# STRWL-S02-V00-12VProtection.net
KiCad netlist of a schematic drawn in Altium Designer
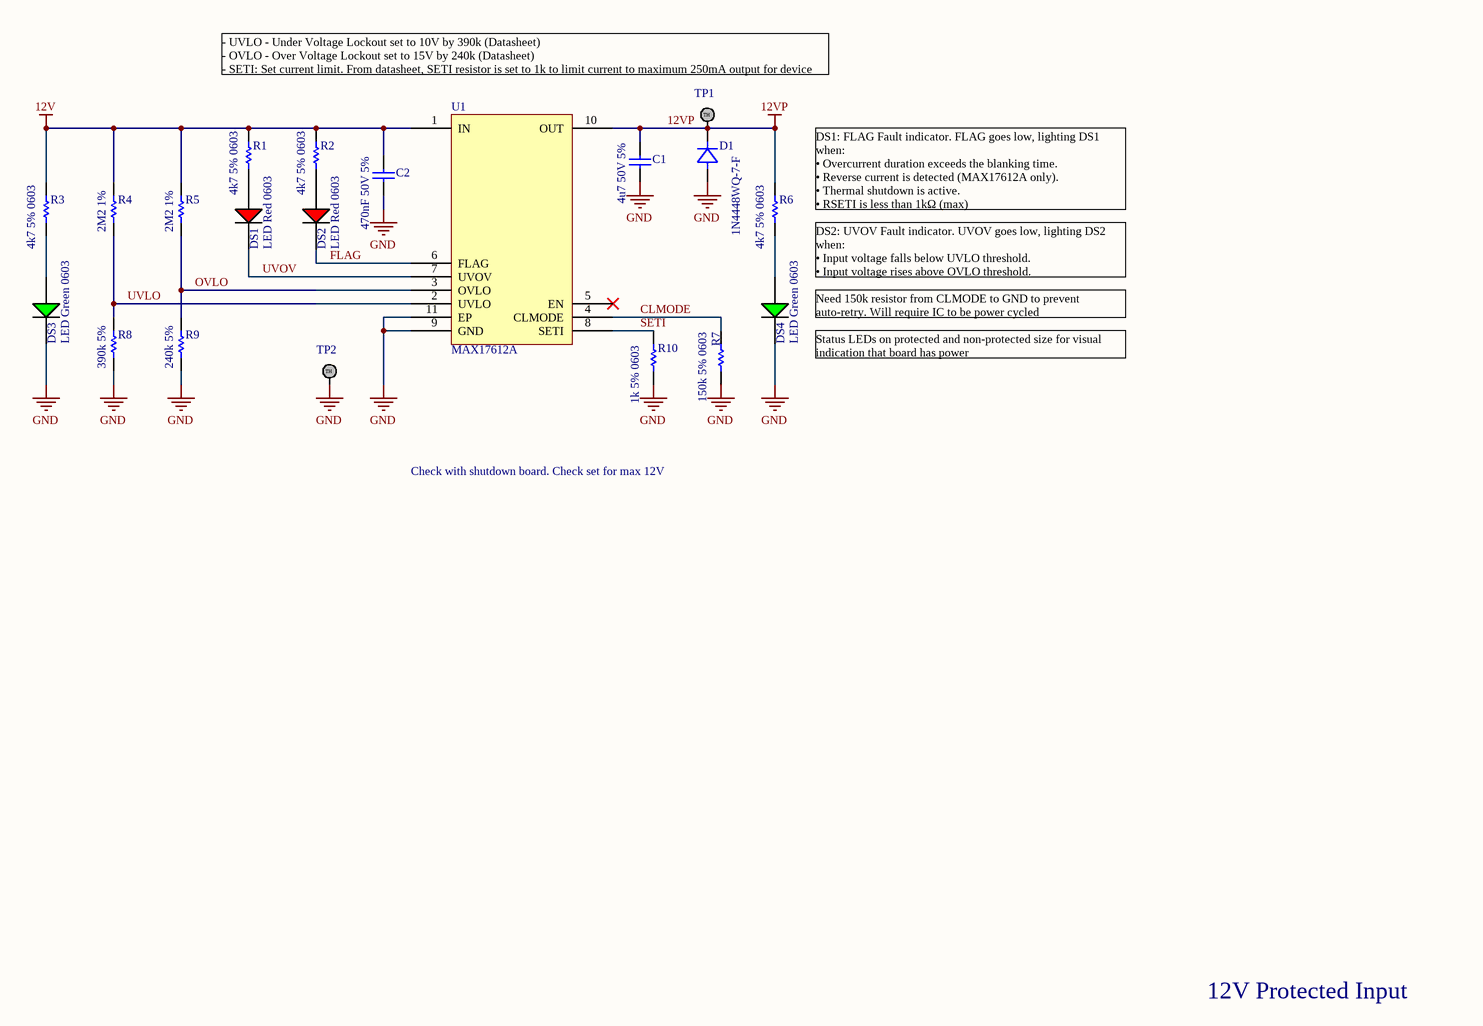
[diagram p0: STRWL-S02-V00-12VProtection.SchDoc]

(export (version "E")
  (design (tool "Eeschema 10.0.6"))
  (components
    (comp (ref "C1")
      (value "4u7 50V 5%")
      (footprint "Cap_Ceramic_0603")
      (description "Capacitor, Ceramic, SMD, 4u7, 50V, 5%, X7R, 0603")
      (libsource (lib "StandardCapacitors") (part "4u7 50V 5% X7R 0603"))
    )
    (comp (ref "C2")
      (value "470nF 50V 5%")
      (footprint "Cap_Ceramic_0603")
      (description "Capacitor, Ceramic, SMD, 470nF, 50V, 5%, X7R, 0603")
      (libsource (lib "StandardCapacitors") (part "470nF 50V 5% X7R 0603"))
    )
    (comp (ref "D1")
      (value "1N4448WQ-7-F")
      (footprint "SMA")
      (description "Diode, SMD, 75V, 5%, 250mA, SOD123")
      (fields
        (field (name "MANUFACTURER") "ON Semiconductor / Fairchild")
        (field (name "MANUFACTURER PART NUMBER") "1N914BWS")
      )
      (libsource (lib "QUTMS_DiodeLibrary") (part "1N4448WQ-7-F"))
    )
    (comp (ref "DS1")
      (value "LED Red 0603")
      (footprint "LED RED 0603")
      (libsource (lib "QUTMS_LEDLibrary") (part "LED Red 0603"))
    )
    (comp (ref "DS2")
      (value "LED Red 0603")
      (footprint "LED RED 0603")
      (libsource (lib "QUTMS_LEDLibrary") (part "LED Red 0603"))
    )
    (comp (ref "DS3")
      (value "LED Green 0603")
      (footprint "LED GREEN 0603")
      (libsource (lib "QUTMS_LEDLibrary") (part "LED Green 0603"))
    )
    (comp (ref "DS4")
      (value "LED Green 0603")
      (footprint "LED GREEN 0603")
      (libsource (lib "QUTMS_LEDLibrary") (part "LED Green 0603"))
    )
    (comp (ref "R1")
      (value "4k7 5% 0603")
      (footprint "Res_ThinFilm_0603")
      (description "Resistor, SMD, 4k7, 0.1W, 5%, 0603")
      (libsource (lib "StandardResistors") (part "4k7 5% 0603"))
    )
    (comp (ref "R2")
      (value "4k7 5% 0603")
      (footprint "Res_ThinFilm_0603")
      (description "Resistor, SMD, 4k7, 0.1W, 5%, 0603")
      (libsource (lib "StandardResistors") (part "4k7 5% 0603"))
    )
    (comp (ref "R3")
      (value "4k7 5% 0603")
      (footprint "Res_ThinFilm_0603")
      (description "Resistor, SMD, 4k7, 0.1W, 5%, 0603")
      (libsource (lib "StandardResistors") (part "4k7 5% 0603"))
    )
    (comp (ref "R4")
      (value "2M2 1%")
      (footprint "Res_ThinFilm_0603")
      (description "Resistor, SMD, 2M2, 0.125W, 1%, 0603")
      (libsource (lib "StandardResistors") (part "2M2 1% 0603"))
    )
    (comp (ref "R5")
      (value "2M2 1%")
      (footprint "Res_ThinFilm_0603")
      (description "Resistor, SMD, 2M2, 0.125W, 1%, 0603")
      (libsource (lib "StandardResistors") (part "2M2 1% 0603"))
    )
    (comp (ref "R6")
      (value "4k7 5% 0603")
      (footprint "Res_ThinFilm_0603")
      (description "Resistor, SMD, 4k7, 0.1W, 5%, 0603")
      (libsource (lib "StandardResistors") (part "4k7 5% 0603"))
    )
    (comp (ref "R7")
      (value "150k 5% 0603")
      (footprint "Res_ThinFilm_0603")
      (description "Resistor, SMD, 150k, 0.1W, 5%, 0603")
      (libsource (lib "StandardResistors") (part "150k 5%, 0603"))
    )
    (comp (ref "R8")
      (value "390k 5%")
      (footprint "Res_ThinFilm_0603")
      (description "Resistor, SMD, 390k, 0.1W, 5%, 0603")
      (libsource (lib "StandardResistors") (part "390k 5% 0603"))
    )
    (comp (ref "R9")
      (value "240k 5%")
      (footprint "Res_ThinFilm_0603")
      (description "Resistor, SMD, 240k, 0.1W, 5%, 0603")
      (libsource (lib "StandardResistors") (part "240k 5% 0603"))
    )
    (comp (ref "R10")
      (value "1k 5% 0603")
      (footprint "Res_ThinFilm_0603")
      (description "Resistor, SMD, 1k, 0.1W, 5%, 0603")
      (libsource (lib "StandardResistors") (part "1k 5% 0603"))
    )
    (comp (ref "TP1")
      (value "TestPoint")
      (footprint "TestPointSMD")
      (libsource (lib "StandardTest") (part "TestPoint"))
    )
    (comp (ref "TP2")
      (value "TestPoint")
      (footprint "TestPointSMD")
      (libsource (lib "StandardTest") (part "TestPoint"))
    )
    (comp (ref "U1")
      (value "MAX17612A")
      (footprint "MAX17612A")
      (description "4.5V to 60V, 250mA Current-Limiter with OV, UV, and Reverse Protection")
      (libsource (lib "QUTMS-MCISOLibrary") (part "MAX17612A"))
    )
  )
  (nets
    (net (code "1") (name "/CLMODE") (class "Default")
      (node (ref "R7") (pin "2") (pinfunction "2_2") (pintype "passive"))
      (node (ref "U1") (pin "4") (pinfunction "CLMODE_4") (pintype "passive"))
    )
    (net (code "2") (name "/FLAG") (class "Default")
      (node (ref "DS2") (pin "2") (pinfunction "C_2") (pintype "passive"))
      (node (ref "U1") (pin "6") (pinfunction "FLAG_6") (pintype "passive"))
    )
    (net (code "3") (name "/OVLO") (class "Default")
      (node (ref "R5") (pin "1") (pinfunction "1_1") (pintype "passive"))
      (node (ref "R9") (pin "2") (pinfunction "2_2") (pintype "passive"))
      (node (ref "U1") (pin "3") (pinfunction "OVLO_3") (pintype "passive"))
    )
    (net (code "4") (name "/SETI") (class "Default")
      (node (ref "R10") (pin "2") (pinfunction "2_2") (pintype "passive"))
      (node (ref "U1") (pin "8") (pinfunction "SETI_8") (pintype "passive"))
    )
    (net (code "5") (name "/UVLO") (class "Default")
      (node (ref "R4") (pin "1") (pinfunction "1_1") (pintype "passive"))
      (node (ref "R8") (pin "2") (pinfunction "2_2") (pintype "passive"))
      (node (ref "U1") (pin "2") (pinfunction "UVLO_2") (pintype "passive"))
    )
    (net (code "6") (name "/UVOV") (class "Default")
      (node (ref "DS1") (pin "2") (pinfunction "C_2") (pintype "passive"))
      (node (ref "U1") (pin "7") (pinfunction "UVOV_7") (pintype "passive"))
    )
    (net (code "7") (name "12V") (class "Default")
      (node (ref "C2") (pin "2") (pinfunction "2_2") (pintype "passive"))
      (node (ref "R1") (pin "2") (pinfunction "2_2") (pintype "passive"))
      (node (ref "R2") (pin "2") (pinfunction "2_2") (pintype "passive"))
      (node (ref "R3") (pin "2") (pinfunction "2_2") (pintype "passive"))
      (node (ref "R4") (pin "2") (pinfunction "2_2") (pintype "passive"))
      (node (ref "R5") (pin "2") (pinfunction "2_2") (pintype "passive"))
      (node (ref "U1") (pin "1") (pinfunction "IN_1") (pintype "passive"))
    )
    (net (code "8") (name "12VP") (class "Default")
      (node (ref "C1") (pin "2") (pinfunction "2_2") (pintype "passive"))
      (node (ref "D1") (pin "K") (pinfunction "Cathode_K") (pintype "passive"))
      (node (ref "R6") (pin "2") (pinfunction "2_2") (pintype "passive"))
      (node (ref "TP1") (pin "1") (pinfunction "1_1") (pintype "passive"))
      (node (ref "U1") (pin "10") (pinfunction "OUT_10") (pintype "passive"))
    )
    (net (code "9") (name "GND") (class "Default")
      (node (ref "C1") (pin "1") (pinfunction "1_1") (pintype "passive"))
      (node (ref "C2") (pin "1") (pinfunction "1_1") (pintype "passive"))
      (node (ref "D1") (pin "A") (pinfunction "Anode_A") (pintype "passive"))
      (node (ref "DS3") (pin "2") (pinfunction "C_2") (pintype "passive"))
      (node (ref "DS4") (pin "2") (pinfunction "C_2") (pintype "passive"))
      (node (ref "R10") (pin "1") (pinfunction "1_1") (pintype "passive"))
      (node (ref "R7") (pin "1") (pinfunction "1_1") (pintype "passive"))
      (node (ref "R8") (pin "1") (pinfunction "1_1") (pintype "passive"))
      (node (ref "R9") (pin "1") (pinfunction "1_1") (pintype "passive"))
      (node (ref "TP2") (pin "1") (pinfunction "1_1") (pintype "passive"))
      (node (ref "U1") (pin "11") (pinfunction "EP_11") (pintype "passive"))
      (node (ref "U1") (pin "9") (pinfunction "GND_9") (pintype "passive"))
    )
    (net (code "10") (name "Net-(DS1-A)") (class "Default")
      (node (ref "DS1") (pin "1") (pinfunction "A_1") (pintype "passive"))
      (node (ref "R1") (pin "1") (pinfunction "1_1") (pintype "passive"))
    )
    (net (code "11") (name "Net-(DS2-A)") (class "Default")
      (node (ref "DS2") (pin "1") (pinfunction "A_1") (pintype "passive"))
      (node (ref "R2") (pin "1") (pinfunction "1_1") (pintype "passive"))
    )
    (net (code "12") (name "Net-(DS3-A)") (class "Default")
      (node (ref "DS3") (pin "1") (pinfunction "A_1") (pintype "passive"))
      (node (ref "R3") (pin "1") (pinfunction "1_1") (pintype "passive"))
    )
    (net (code "13") (name "Net-(DS4-A)") (class "Default")
      (node (ref "DS4") (pin "1") (pinfunction "A_1") (pintype "passive"))
      (node (ref "R6") (pin "1") (pinfunction "1_1") (pintype "passive"))
    )
    (net (code "14") (name "unconnected-(U1-EN-Pad5)") (class "Default")
      (node (ref "U1") (pin "5") (pinfunction "EN_5") (pintype "passive+no_connect"))
    )
  )
)
